# motorcontrol.net
KiCad netlist of a schematic drawn in EAGLE
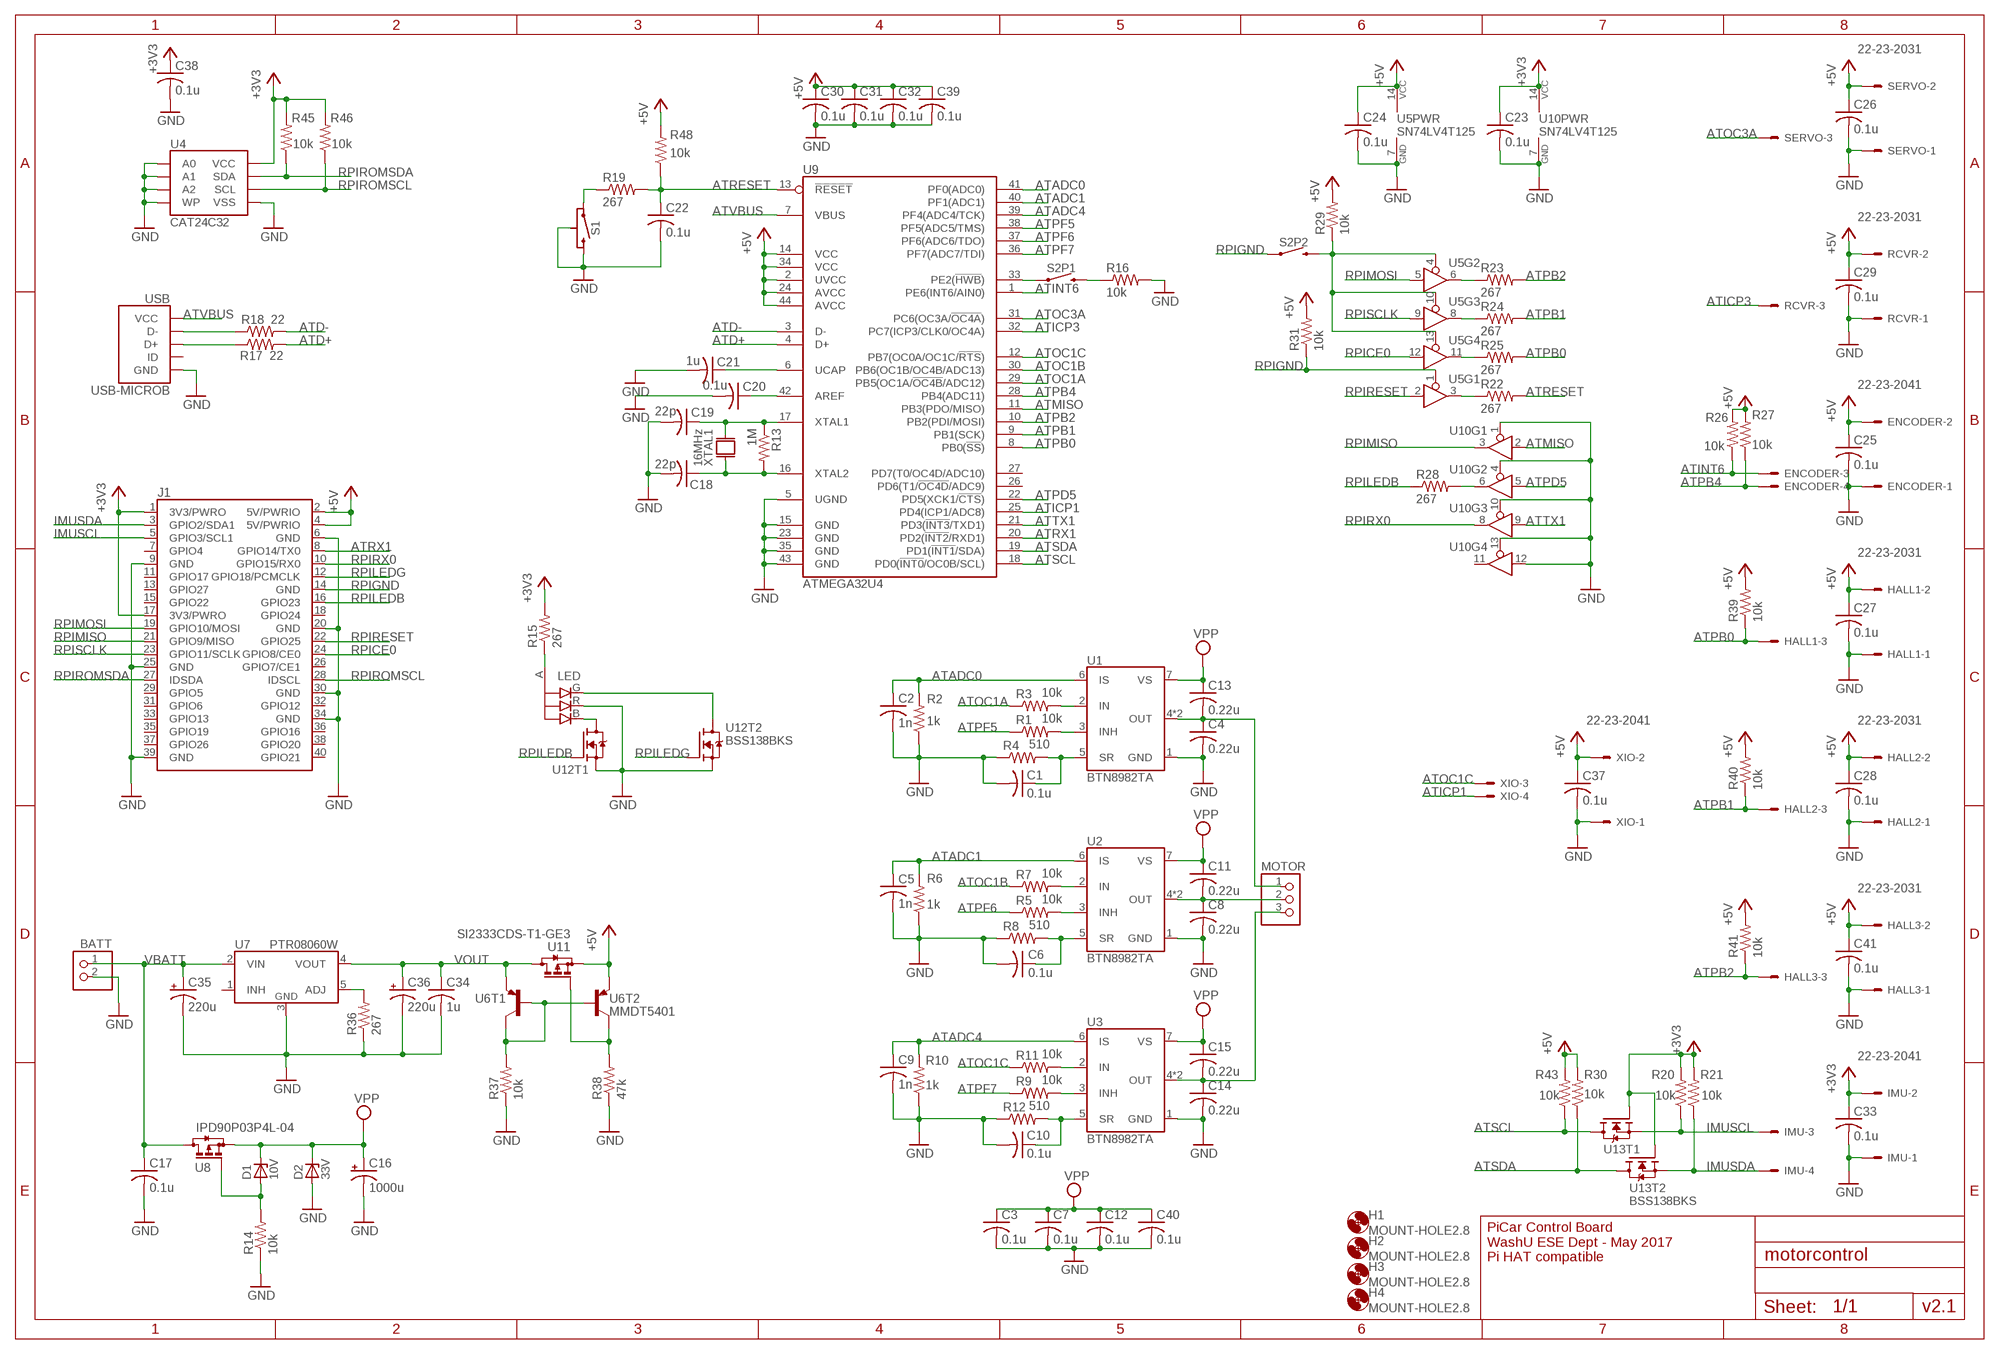
[diagram p0: schematic, sheet 1]

(export (version "E")
  (design (tool "Eeschema 10.0.6"))
  (components
    (comp (ref "BATT")
      (value "ULTRAFIT_2CIRCVCLIP")
      (footprint "eagle-import:ULTRAFIT_2CIRC_VERTCLIP")
      (libsource (lib "eagle-import") (part "ULTRAFIT_2CIRCVCLIP"))
    )
    (comp (ref "C1")
      (value "0.1u")
      (footprint "eagle-import:C1206")
      (libsource (lib "eagle-import") (part "C-USC1206"))
    )
    (comp (ref "C2")
      (value "1n")
      (footprint "eagle-import:C1206")
      (libsource (lib "eagle-import") (part "C-USC1206"))
    )
    (comp (ref "C3")
      (value "0.1u")
      (footprint "eagle-import:C1206")
      (libsource (lib "eagle-import") (part "C-USC1206"))
    )
    (comp (ref "C4")
      (value "0.22u")
      (footprint "eagle-import:C1206")
      (libsource (lib "eagle-import") (part "C-USC1206"))
    )
    (comp (ref "C5")
      (value "1n")
      (footprint "eagle-import:C1206")
      (libsource (lib "eagle-import") (part "C-USC1206"))
    )
    (comp (ref "C6")
      (value "0.1u")
      (footprint "eagle-import:C1206")
      (libsource (lib "eagle-import") (part "C-USC1206"))
    )
    (comp (ref "C7")
      (value "0.1u")
      (footprint "eagle-import:C1206")
      (libsource (lib "eagle-import") (part "C-USC1206"))
    )
    (comp (ref "C8")
      (value "0.22u")
      (footprint "eagle-import:C1206")
      (libsource (lib "eagle-import") (part "C-USC1206"))
    )
    (comp (ref "C9")
      (value "1n")
      (footprint "eagle-import:C1206")
      (libsource (lib "eagle-import") (part "C-USC1206"))
    )
    (comp (ref "C10")
      (value "0.1u")
      (footprint "eagle-import:C1206")
      (libsource (lib "eagle-import") (part "C-USC1206"))
    )
    (comp (ref "C11")
      (value "0.22u")
      (footprint "eagle-import:C1206")
      (libsource (lib "eagle-import") (part "C-USC1206"))
    )
    (comp (ref "C12")
      (value "0.1u")
      (footprint "eagle-import:C1206")
      (libsource (lib "eagle-import") (part "C-USC1206"))
    )
    (comp (ref "C13")
      (value "0.22u")
      (footprint "eagle-import:C1206")
      (libsource (lib "eagle-import") (part "C-USC1206"))
    )
    (comp (ref "C14")
      (value "0.22u")
      (footprint "eagle-import:C1206")
      (libsource (lib "eagle-import") (part "C-USC1206"))
    )
    (comp (ref "C15")
      (value "0.22u")
      (footprint "eagle-import:C1206")
      (libsource (lib "eagle-import") (part "C-USC1206"))
    )
    (comp (ref "C16")
      (value "1000u")
      (footprint "eagle-import:E5-10,5")
      (libsource (lib "eagle-import") (part "CPOL-USE5-10.5"))
    )
    (comp (ref "C17")
      (value "0.1u")
      (footprint "eagle-import:C1206")
      (libsource (lib "eagle-import") (part "C-USC1206"))
    )
    (comp (ref "C18")
      (value "22p")
      (footprint "eagle-import:C1206")
      (libsource (lib "eagle-import") (part "C-USC1206"))
    )
    (comp (ref "C19")
      (value "22p")
      (footprint "eagle-import:C1206")
      (libsource (lib "eagle-import") (part "C-USC1206"))
    )
    (comp (ref "C20")
      (value "0.1u")
      (footprint "eagle-import:C1206")
      (libsource (lib "eagle-import") (part "C-USC1206"))
    )
    (comp (ref "C21")
      (value "1u")
      (footprint "eagle-import:C1206")
      (libsource (lib "eagle-import") (part "C-USC1206"))
    )
    (comp (ref "C22")
      (value "0.1u")
      (footprint "eagle-import:C1206")
      (libsource (lib "eagle-import") (part "C-USC1206"))
    )
    (comp (ref "C23")
      (value "0.1u")
      (footprint "eagle-import:C1206")
      (libsource (lib "eagle-import") (part "C-USC1206"))
    )
    (comp (ref "C24")
      (value "0.1u")
      (footprint "eagle-import:C1206")
      (libsource (lib "eagle-import") (part "C-USC1206"))
    )
    (comp (ref "C25")
      (value "0.1u")
      (footprint "eagle-import:C1206")
      (libsource (lib "eagle-import") (part "C-USC1206"))
    )
    (comp (ref "C26")
      (value "0.1u")
      (footprint "eagle-import:C1206")
      (libsource (lib "eagle-import") (part "C-USC1206"))
    )
    (comp (ref "C27")
      (value "0.1u")
      (footprint "eagle-import:C1206")
      (libsource (lib "eagle-import") (part "C-USC1206"))
    )
    (comp (ref "C28")
      (value "0.1u")
      (footprint "eagle-import:C1206")
      (libsource (lib "eagle-import") (part "C-USC1206"))
    )
    (comp (ref "C29")
      (value "0.1u")
      (footprint "eagle-import:C1206")
      (libsource (lib "eagle-import") (part "C-USC1206"))
    )
    (comp (ref "C30")
      (value "0.1u")
      (footprint "eagle-import:C1206")
      (libsource (lib "eagle-import") (part "C-USC1206"))
    )
    (comp (ref "C31")
      (value "0.1u")
      (footprint "eagle-import:C1206")
      (libsource (lib "eagle-import") (part "C-USC1206"))
    )
    (comp (ref "C32")
      (value "0.1u")
      (footprint "eagle-import:C1206")
      (libsource (lib "eagle-import") (part "C-USC1206"))
    )
    (comp (ref "C33")
      (value "0.1u")
      (footprint "eagle-import:C1206")
      (libsource (lib "eagle-import") (part "C-USC1206"))
    )
    (comp (ref "C34")
      (value "1u")
      (footprint "eagle-import:C1206")
      (libsource (lib "eagle-import") (part "C-USC1206"))
    )
    (comp (ref "C35")
      (value "220u")
      (footprint "eagle-import:E3,5-8")
      (libsource (lib "eagle-import") (part "CPOL-USE3.5-8"))
    )
    (comp (ref "C36")
      (value "220u")
      (footprint "eagle-import:E3,5-8")
      (libsource (lib "eagle-import") (part "CPOL-USE3.5-8"))
    )
    (comp (ref "C37")
      (value "0.1u")
      (footprint "eagle-import:C1206")
      (libsource (lib "eagle-import") (part "C-USC1206"))
    )
    (comp (ref "C38")
      (value "0.1u")
      (footprint "eagle-import:C1206")
      (libsource (lib "eagle-import") (part "C-USC1206"))
    )
    (comp (ref "C39")
      (value "0.1u")
      (footprint "eagle-import:C1206")
      (libsource (lib "eagle-import") (part "C-USC1206"))
    )
    (comp (ref "C40")
      (value "0.1u")
      (footprint "eagle-import:C1206")
      (libsource (lib "eagle-import") (part "C-USC1206"))
    )
    (comp (ref "C41")
      (value "0.1u")
      (footprint "eagle-import:C1206")
      (libsource (lib "eagle-import") (part "C-USC1206"))
    )
    (comp (ref "D1")
      (value "10V")
      (footprint "eagle-import:SOD123")
      (libsource (lib "eagle-import") (part "ZENER_DIODESOD123"))
    )
    (comp (ref "D2")
      (value "33V")
      (footprint "eagle-import:SMA")
      (libsource (lib "eagle-import") (part "ZENER_DIODESMA"))
    )
    (comp (ref "ENCODER")
      (value "22-23-2041")
      (footprint "eagle-import:22-23-2041")
      (fields (field (name "MF") "MOLEX"))
      (libsource (lib "eagle-import") (part "22-23-2041"))
    )
    (comp (ref "H1")
      (value "MOUNT-HOLE2.8")
      (footprint "eagle-import:2,8")
      (libsource (lib "eagle-import") (part "MOUNT-HOLE2.8"))
    )
    (comp (ref "H2")
      (value "MOUNT-HOLE2.8")
      (footprint "eagle-import:2,8")
      (libsource (lib "eagle-import") (part "MOUNT-HOLE2.8"))
    )
    (comp (ref "H3")
      (value "MOUNT-HOLE2.8")
      (footprint "eagle-import:2,8")
      (libsource (lib "eagle-import") (part "MOUNT-HOLE2.8"))
    )
    (comp (ref "H4")
      (value "MOUNT-HOLE2.8")
      (footprint "eagle-import:2,8")
      (libsource (lib "eagle-import") (part "MOUNT-HOLE2.8"))
    )
    (comp (ref "HALL1")
      (value "22-23-2031")
      (footprint "eagle-import:22-23-2031")
      (fields (field (name "MF") "MOLEX"))
      (libsource (lib "eagle-import") (part "22-23-2031"))
    )
    (comp (ref "HALL2")
      (value "22-23-2031")
      (footprint "eagle-import:22-23-2031")
      (fields (field (name "MF") "MOLEX"))
      (libsource (lib "eagle-import") (part "22-23-2031"))
    )
    (comp (ref "HALL3")
      (value "22-23-2031")
      (footprint "eagle-import:22-23-2031")
      (fields (field (name "MF") "MOLEX"))
      (libsource (lib "eagle-import") (part "22-23-2031"))
    )
    (comp (ref "IMU")
      (value "22-23-2041")
      (footprint "eagle-import:22-23-2041")
      (fields (field (name "MF") "MOLEX"))
      (libsource (lib "eagle-import") (part "22-23-2041"))
    )
    (comp (ref "J1")
      (value "RPIHEADER_2.54-SMD")
      (footprint "eagle-import:RPI_SMD")
      (libsource (lib "eagle-import") (part "RPIHEADER_2.54-SMD"))
    )
    (comp (ref "LED")
      (value "LED_3COLOR_COMMONA1411")
      (footprint "eagle-import:150141M173100")
      (libsource (lib "eagle-import") (part "LED_3COLOR_COMMONA1411"))
    )
    (comp (ref "MOTOR")
      (value "ULTRAFIT_3CIRCVCLIP")
      (footprint "eagle-import:ULTRAFIT_3CIRC_VERTCLIP")
      (libsource (lib "eagle-import") (part "ULTRAFIT_3CIRCVCLIP"))
    )
    (comp (ref "R1")
      (value "10k")
      (footprint "eagle-import:R1206")
      (libsource (lib "eagle-import") (part "R-US_R1206"))
    )
    (comp (ref "R2")
      (value "1k")
      (footprint "eagle-import:R1206")
      (libsource (lib "eagle-import") (part "R-US_R1206"))
    )
    (comp (ref "R3")
      (value "10k")
      (footprint "eagle-import:R1206")
      (libsource (lib "eagle-import") (part "R-US_R1206"))
    )
    (comp (ref "R4")
      (value "510")
      (footprint "eagle-import:R1206")
      (libsource (lib "eagle-import") (part "R-US_R1206"))
    )
    (comp (ref "R5")
      (value "10k")
      (footprint "eagle-import:R1206")
      (libsource (lib "eagle-import") (part "R-US_R1206"))
    )
    (comp (ref "R6")
      (value "1k")
      (footprint "eagle-import:R1206")
      (libsource (lib "eagle-import") (part "R-US_R1206"))
    )
    (comp (ref "R7")
      (value "10k")
      (footprint "eagle-import:R1206")
      (libsource (lib "eagle-import") (part "R-US_R1206"))
    )
    (comp (ref "R8")
      (value "510")
      (footprint "eagle-import:R1206")
      (libsource (lib "eagle-import") (part "R-US_R1206"))
    )
    (comp (ref "R9")
      (value "10k")
      (footprint "eagle-import:R1206")
      (libsource (lib "eagle-import") (part "R-US_R1206"))
    )
    (comp (ref "R10")
      (value "1k")
      (footprint "eagle-import:R1206")
      (libsource (lib "eagle-import") (part "R-US_R1206"))
    )
    (comp (ref "R11")
      (value "10k")
      (footprint "eagle-import:R1206")
      (libsource (lib "eagle-import") (part "R-US_R1206"))
    )
    (comp (ref "R12")
      (value "510")
      (footprint "eagle-import:R1206")
      (libsource (lib "eagle-import") (part "R-US_R1206"))
    )
    (comp (ref "R13")
      (value "1M")
      (footprint "eagle-import:R1206")
      (libsource (lib "eagle-import") (part "R-US_R1206"))
    )
    (comp (ref "R14")
      (value "10k")
      (footprint "eagle-import:R1206")
      (libsource (lib "eagle-import") (part "R-US_R1206"))
    )
    (comp (ref "R15")
      (value "267")
      (footprint "eagle-import:R1206")
      (libsource (lib "eagle-import") (part "R-US_R1206"))
    )
    (comp (ref "R16")
      (value "10k")
      (footprint "eagle-import:R1206")
      (libsource (lib "eagle-import") (part "R-US_R1206"))
    )
    (comp (ref "R17")
      (value "22")
      (footprint "eagle-import:R1206")
      (libsource (lib "eagle-import") (part "R-US_R1206"))
    )
    (comp (ref "R18")
      (value "22")
      (footprint "eagle-import:R1206")
      (libsource (lib "eagle-import") (part "R-US_R1206"))
    )
    (comp (ref "R19")
      (value "267")
      (footprint "eagle-import:R1206")
      (libsource (lib "eagle-import") (part "R-US_R1206"))
    )
    (comp (ref "R20")
      (value "10k")
      (footprint "eagle-import:R1206")
      (libsource (lib "eagle-import") (part "R-US_R1206"))
    )
    (comp (ref "R21")
      (value "10k")
      (footprint "eagle-import:R1206")
      (libsource (lib "eagle-import") (part "R-US_R1206"))
    )
    (comp (ref "R22")
      (value "267")
      (footprint "eagle-import:R1206")
      (libsource (lib "eagle-import") (part "R-US_R1206"))
    )
    (comp (ref "R23")
      (value "267")
      (footprint "eagle-import:R1206")
      (libsource (lib "eagle-import") (part "R-US_R1206"))
    )
    (comp (ref "R24")
      (value "267")
      (footprint "eagle-import:R1206")
      (libsource (lib "eagle-import") (part "R-US_R1206"))
    )
    (comp (ref "R25")
      (value "267")
      (footprint "eagle-import:R1206")
      (libsource (lib "eagle-import") (part "R-US_R1206"))
    )
    (comp (ref "R26")
      (value "10k")
      (footprint "eagle-import:R1206")
      (libsource (lib "eagle-import") (part "R-US_R1206"))
    )
    (comp (ref "R27")
      (value "10k")
      (footprint "eagle-import:R1206")
      (libsource (lib "eagle-import") (part "R-US_R1206"))
    )
    (comp (ref "R28")
      (value "267")
      (footprint "eagle-import:R1206")
      (libsource (lib "eagle-import") (part "R-US_R1206"))
    )
    (comp (ref "R29")
      (value "10k")
      (footprint "eagle-import:R1206")
      (libsource (lib "eagle-import") (part "R-US_R1206"))
    )
    (comp (ref "R30")
      (value "10k")
      (footprint "eagle-import:R1206")
      (libsource (lib "eagle-import") (part "R-US_R1206"))
    )
    (comp (ref "R31")
      (value "10k")
      (footprint "eagle-import:R1206")
      (libsource (lib "eagle-import") (part "R-US_R1206"))
    )
    (comp (ref "R36")
      (value "267")
      (footprint "eagle-import:R1206")
      (libsource (lib "eagle-import") (part "R-US_R1206"))
    )
    (comp (ref "R37")
      (value "10k")
      (footprint "eagle-import:R1206")
      (libsource (lib "eagle-import") (part "R-US_R1206"))
    )
    (comp (ref "R38")
      (value "47k")
      (footprint "eagle-import:R1206")
      (libsource (lib "eagle-import") (part "R-US_R1206"))
    )
    (comp (ref "R39")
      (value "10k")
      (footprint "eagle-import:R1206")
      (libsource (lib "eagle-import") (part "R-US_R1206"))
    )
    (comp (ref "R40")
      (value "10k")
      (footprint "eagle-import:R1206")
      (libsource (lib "eagle-import") (part "R-US_R1206"))
    )
    (comp (ref "R41")
      (value "10k")
      (footprint "eagle-import:R1206")
      (libsource (lib "eagle-import") (part "R-US_R1206"))
    )
    (comp (ref "R43")
      (value "10k")
      (footprint "eagle-import:R1206")
      (libsource (lib "eagle-import") (part "R-US_R1206"))
    )
    (comp (ref "R45")
      (value "10k")
      (footprint "eagle-import:R1206")
      (libsource (lib "eagle-import") (part "R-US_R1206"))
    )
    (comp (ref "R46")
      (value "10k")
      (footprint "eagle-import:R1206")
      (libsource (lib "eagle-import") (part "R-US_R1206"))
    )
    (comp (ref "R48")
      (value "10k")
      (footprint "eagle-import:R1206")
      (libsource (lib "eagle-import") (part "R-US_R1206"))
    )
    (comp (ref "RCVR")
      (value "22-23-2031")
      (footprint "eagle-import:22-23-2031")
      (fields (field (name "MF") "MOLEX"))
      (libsource (lib "eagle-import") (part "22-23-2031"))
    )
    (comp (ref "S1")
      (value "SWITCH-GND")
      (footprint "eagle-import:B3F-312X")
      (libsource (lib "eagle-import") (part "SWITCH-GND"))
    )
    (comp (ref "S2")
      (value "A6HF-2DIP")
      (footprint "eagle-import:A6HF-2DIP")
      (libsource (lib "eagle-import") (part "A6HF-2DIP"))
    )
    (comp (ref "SERVO")
      (value "22-23-2031")
      (footprint "eagle-import:22-23-2031")
      (fields (field (name "MF") "MOLEX"))
      (libsource (lib "eagle-import") (part "22-23-2031"))
    )
    (comp (ref "U1")
      (value "BTN8982TA")
      (footprint "eagle-import:TO263-7")
      (libsource (lib "eagle-import") (part "BTN8982TA"))
    )
    (comp (ref "U2")
      (value "BTN8982TA")
      (footprint "eagle-import:TO263-7")
      (libsource (lib "eagle-import") (part "BTN8982TA"))
    )
    (comp (ref "U3")
      (value "BTN8982TA")
      (footprint "eagle-import:TO263-7")
      (libsource (lib "eagle-import") (part "BTN8982TA"))
    )
    (comp (ref "U4")
      (value "CAT24C32")
      (footprint "eagle-import:SOIC8")
      (libsource (lib "eagle-import") (part "CAT24C32"))
    )
    (comp (ref "U5")
      (value "SN74LV4T125")
      (footprint "eagle-import:TSSOP14")
      (libsource (lib "eagle-import") (part "SN74LV4T125"))
    )
    (comp (ref "U6")
      (value "MMDT5401")
      (footprint "eagle-import:SOT363")
      (libsource (lib "eagle-import") (part "MMDT5401"))
    )
    (comp (ref "U7")
      (value "PTR08060W")
      (footprint "eagle-import:EDP_MODULE")
      (libsource (lib "eagle-import") (part "PTR08060W"))
    )
    (comp (ref "U8")
      (value "IPD90P03P4L-04")
      (footprint "eagle-import:TO252-3-11")
      (libsource (lib "eagle-import") (part "IPD90P03P4L-04"))
    )
    (comp (ref "U9")
      (value "ATMEGA32U4")
      (footprint "eagle-import:TQFP44")
      (libsource (lib "eagle-import") (part "ATMEGA32U4"))
    )
    (comp (ref "U10")
      (value "SN74LV4T125")
      (footprint "eagle-import:TSSOP14")
      (libsource (lib "eagle-import") (part "SN74LV4T125"))
    )
    (comp (ref "U11")
      (value "SI2333CDS-T1-GE3")
      (footprint "eagle-import:SOT23-3")
      (libsource (lib "eagle-import") (part "SI2333CDS-T1-GE3"))
    )
    (comp (ref "U12")
      (value "BSS138BKS")
      (footprint "eagle-import:SOT363")
      (libsource (lib "eagle-import") (part "BSS138BKS"))
    )
    (comp (ref "U13")
      (value "BSS138BKS")
      (footprint "eagle-import:SOT363")
      (libsource (lib "eagle-import") (part "BSS138BKS"))
    )
    (comp (ref "USB")
      (value "USB-MICROB")
      (footprint "eagle-import:FCI-10103594-0001LF")
      (libsource (lib "eagle-import") (part "USB-MICROB"))
    )
    (comp (ref "XIO")
      (value "22-23-2041")
      (footprint "eagle-import:22-23-2041")
      (fields (field (name "MF") "MOLEX"))
      (libsource (lib "eagle-import") (part "22-23-2041"))
    )
    (comp (ref "XTAL1")
      (value "16MHz")
      (footprint "eagle-import:ABLS7M2")
      (libsource (lib "eagle-import") (part "XTALABLS7M2"))
    )
  )
  (nets
    (net (code "1") (name "+3V3") (class "Default")
      (node (ref "C23") (pin "1") (pinfunction "1_1") (pintype "passive"))
      (node (ref "C33") (pin "1") (pinfunction "1_1") (pintype "passive"))
      (node (ref "C38") (pin "1") (pinfunction "1_1") (pintype "passive"))
      (node (ref "IMU") (pin "2") (pinfunction "S_2") (pintype "passive"))
      (node (ref "J1") (pin "1") (pinfunction "3V3/PWRO_1") (pintype "passive"))
      (node (ref "J1") (pin "17") (pinfunction "3V3/PWRO_17") (pintype "passive"))
      (node (ref "R15") (pin "2") (pinfunction "2_2") (pintype "passive"))
      (node (ref "R20") (pin "2") (pinfunction "2_2") (pintype "passive"))
      (node (ref "R21") (pin "2") (pinfunction "2_2") (pintype "passive"))
      (node (ref "R45") (pin "2") (pinfunction "2_2") (pintype "passive"))
      (node (ref "R46") (pin "2") (pinfunction "2_2") (pintype "passive"))
      (node (ref "U10") (pin "14") (pinfunction "VCC_14") (pintype "power_in"))
      (node (ref "U13") (pin "2") (pinfunction "G_2") (pintype "passive"))
      (node (ref "U13") (pin "5") (pinfunction "G_5") (pintype "passive"))
      (node (ref "U4") (pin "8") (pinfunction "VCC_8") (pintype "power_in"))
    )
    (net (code "2") (name "+5V") (class "Default")
      (node (ref "C24") (pin "1") (pinfunction "1_1") (pintype "passive"))
      (node (ref "C25") (pin "1") (pinfunction "1_1") (pintype "passive"))
      (node (ref "C26") (pin "1") (pinfunction "1_1") (pintype "passive"))
      (node (ref "C27") (pin "1") (pinfunction "1_1") (pintype "passive"))
      (node (ref "C28") (pin "1") (pinfunction "1_1") (pintype "passive"))
      (node (ref "C29") (pin "1") (pinfunction "1_1") (pintype "passive"))
      (node (ref "C30") (pin "1") (pinfunction "1_1") (pintype "passive"))
      (node (ref "C31") (pin "1") (pinfunction "1_1") (pintype "passive"))
      (node (ref "C32") (pin "1") (pinfunction "1_1") (pintype "passive"))
      (node (ref "C37") (pin "1") (pinfunction "1_1") (pintype "passive"))
      (node (ref "C39") (pin "1") (pinfunction "1_1") (pintype "passive"))
      (node (ref "C41") (pin "1") (pinfunction "1_1") (pintype "passive"))
      (node (ref "ENCODER") (pin "2") (pinfunction "S_2") (pintype "passive"))
      (node (ref "HALL1") (pin "2") (pinfunction "S_2") (pintype "passive"))
      (node (ref "HALL2") (pin "2") (pinfunction "S_2") (pintype "passive"))
      (node (ref "HALL3") (pin "2") (pinfunction "S_2") (pintype "passive"))
      (node (ref "J1") (pin "2") (pinfunction "5V/PWRIO_2") (pintype "passive"))
      (node (ref "J1") (pin "4") (pinfunction "5V/PWRIO_4") (pintype "passive"))
      (node (ref "R26") (pin "2") (pinfunction "2_2") (pintype "passive"))
      (node (ref "R27") (pin "2") (pinfunction "2_2") (pintype "passive"))
      (node (ref "R29") (pin "2") (pinfunction "2_2") (pintype "passive"))
      (node (ref "R30") (pin "2") (pinfunction "2_2") (pintype "passive"))
      (node (ref "R31") (pin "2") (pinfunction "2_2") (pintype "passive"))
      (node (ref "R39") (pin "2") (pinfunction "2_2") (pintype "passive"))
      (node (ref "R40") (pin "2") (pinfunction "2_2") (pintype "passive"))
      (node (ref "R41") (pin "2") (pinfunction "2_2") (pintype "passive"))
      (node (ref "R43") (pin "2") (pinfunction "2_2") (pintype "passive"))
      (node (ref "R48") (pin "2") (pinfunction "2_2") (pintype "passive"))
      (node (ref "RCVR") (pin "2") (pinfunction "S_2") (pintype "passive"))
      (node (ref "SERVO") (pin "2") (pinfunction "S_2") (pintype "passive"))
      (node (ref "U11") (pin "2") (pinfunction "S_2") (pintype "passive"))
      (node (ref "U5") (pin "14") (pinfunction "VCC_14") (pintype "power_in"))
      (node (ref "U6") (pin "4") (pinfunction "E_4") (pintype "passive"))
      (node (ref "U9") (pin "14") (pinfunction "VCC_14") (pintype "bidirectional"))
      (node (ref "U9") (pin "2") (pinfunction "UVCC_2") (pintype "bidirectional"))
      (node (ref "U9") (pin "24") (pinfunction "AVCC_24") (pintype "bidirectional"))
      (node (ref "U9") (pin "34") (pinfunction "VCC_34") (pintype "bidirectional"))
      (node (ref "U9") (pin "44") (pinfunction "AVCC_44") (pintype "bidirectional"))
      (node (ref "XIO") (pin "2") (pinfunction "S_2") (pintype "passive"))
    )
    (net (code "3") (name "/ATADC0") (class "Default")
      (node (ref "C2") (pin "1") (pinfunction "1_1") (pintype "passive"))
      (node (ref "R2") (pin "2") (pinfunction "2_2") (pintype "passive"))
      (node (ref "U1") (pin "6") (pinfunction "IS_6") (pintype "output"))
      (node (ref "U9") (pin "41") (pinfunction "PF0(ADC0)_41") (pintype "bidirectional"))
    )
    (net (code "4") (name "/ATADC1") (class "Default")
      (node (ref "C5") (pin "1") (pinfunction "1_1") (pintype "passive"))
      (node (ref "R6") (pin "2") (pinfunction "2_2") (pintype "passive"))
      (node (ref "U2") (pin "6") (pinfunction "IS_6") (pintype "output"))
      (node (ref "U9") (pin "40") (pinfunction "PF1(ADC1)_40") (pintype "bidirectional"))
    )
    (net (code "5") (name "/ATADC4") (class "Default")
      (node (ref "C9") (pin "1") (pinfunction "1_1") (pintype "passive"))
      (node (ref "R10") (pin "2") (pinfunction "2_2") (pintype "passive"))
      (node (ref "U3") (pin "6") (pinfunction "IS_6") (pintype "output"))
      (node (ref "U9") (pin "39") (pinfunction "PF4(ADC4/TCK)_39") (pintype "bidirectional"))
    )
    (net (code "6") (name "/ATD+") (class "Default")
      (node (ref "R17") (pin "2") (pinfunction "2_2") (pintype "passive"))
      (node (ref "U9") (pin "4") (pinfunction "D+_4") (pintype "bidirectional"))
    )
    (net (code "7") (name "/ATD-") (class "Default")
      (node (ref "R18") (pin "2") (pinfunction "2_2") (pintype "passive"))
      (node (ref "U9") (pin "3") (pinfunction "D-_3") (pintype "bidirectional"))
    )
    (net (code "8") (name "/ATICP1") (class "Default")
      (node (ref "U9") (pin "25") (pinfunction "PD4(ICP1/ADC8)_25") (pintype "bidirectional"))
      (node (ref "XIO") (pin "4") (pinfunction "S_4") (pintype "passive"))
    )
    (net (code "9") (name "/ATICP3") (class "Default")
      (node (ref "RCVR") (pin "3") (pinfunction "S_3") (pintype "passive"))
      (node (ref "U9") (pin "32") (pinfunction "PC7(ICP3/CLK0/OC4A)_32") (pintype "bidirectional"))
    )
    (net (code "10") (name "/ATINT6") (class "Default")
      (node (ref "ENCODER") (pin "3") (pinfunction "S_3") (pintype "passive"))
      (node (ref "R26") (pin "1") (pinfunction "1_1") (pintype "passive"))
      (node (ref "U9") (pin "1") (pinfunction "PE6(INT6/AIN0)_1") (pintype "bidirectional"))
    )
    (net (code "11") (name "/ATMISO") (class "Default")
      (node (ref "U10") (pin "2") (pinfunction "I_2") (pintype "input"))
      (node (ref "U9") (pin "11") (pinfunction "PB3(PDO/MISO)_11") (pintype "bidirectional"))
    )
    (net (code "12") (name "/ATOC1A") (class "Default")
      (node (ref "R3") (pin "1") (pinfunction "1_1") (pintype "passive"))
      (node (ref "U9") (pin "29") (pinfunction "PB5(OC1A/~{OC4B}/ADC12)_29") (pintype "bidirectional"))
    )
    (net (code "13") (name "/ATOC1B") (class "Default")
      (node (ref "R7") (pin "1") (pinfunction "1_1") (pintype "passive"))
      (node (ref "U9") (pin "30") (pinfunction "PB6(OC1B/OC4B/ADC13)_30") (pintype "bidirectional"))
    )
    (net (code "14") (name "/ATOC1C") (class "Default")
      (node (ref "R11") (pin "1") (pinfunction "1_1") (pintype "passive"))
      (node (ref "U9") (pin "12") (pinfunction "PB7(OC0A/OC1C/~{RTS})_12") (pintype "bidirectional"))
      (node (ref "XIO") (pin "3") (pinfunction "S_3") (pintype "passive"))
    )
    (net (code "15") (name "/ATOC3A") (class "Default")
      (node (ref "SERVO") (pin "3") (pinfunction "S_3") (pintype "passive"))
      (node (ref "U9") (pin "31") (pinfunction "PC6(OC3A/~{OC4A})_31") (pintype "bidirectional"))
    )
    (net (code "16") (name "/ATPB0") (class "Default")
      (node (ref "HALL1") (pin "3") (pinfunction "S_3") (pintype "passive"))
      (node (ref "R25") (pin "2") (pinfunction "2_2") (pintype "passive"))
      (node (ref "R39") (pin "1") (pinfunction "1_1") (pintype "passive"))
      (node (ref "U9") (pin "8") (pinfunction "PB0(~{SS})_8") (pintype "bidirectional"))
    )
    (net (code "17") (name "/ATPB1") (class "Default")
      (node (ref "HALL2") (pin "3") (pinfunction "S_3") (pintype "passive"))
      (node (ref "R24") (pin "2") (pinfunction "2_2") (pintype "passive"))
      (node (ref "R40") (pin "1") (pinfunction "1_1") (pintype "passive"))
      (node (ref "U9") (pin "9") (pinfunction "PB1(SCK)_9") (pintype "bidirectional"))
    )
    (net (code "18") (name "/ATPB2") (class "Default")
      (node (ref "HALL3") (pin "3") (pinfunction "S_3") (pintype "passive"))
      (node (ref "R23") (pin "2") (pinfunction "2_2") (pintype "passive"))
      (node (ref "R41") (pin "1") (pinfunction "1_1") (pintype "passive"))
      (node (ref "U9") (pin "10") (pinfunction "PB2(PDI/MOSI)_10") (pintype "bidirectional"))
    )
    (net (code "19") (name "/ATPB4") (class "Default")
      (node (ref "ENCODER") (pin "4") (pinfunction "S_4") (pintype "passive"))
      (node (ref "R27") (pin "1") (pinfunction "1_1") (pintype "passive"))
      (node (ref "U9") (pin "28") (pinfunction "PB4(ADC11)_28") (pintype "bidirectional"))
    )
    (net (code "20") (name "/ATPD5") (class "Default")
      (node (ref "U10") (pin "5") (pinfunction "I_5") (pintype "input"))
      (node (ref "U9") (pin "22") (pinfunction "PD5(XCK1/~{CTS})_22") (pintype "bidirectional"))
    )
    (net (code "21") (name "/ATPF5") (class "Default")
      (node (ref "R1") (pin "1") (pinfunction "1_1") (pintype "passive"))
      (node (ref "U9") (pin "38") (pinfunction "PF5(ADC5/TMS)_38") (pintype "bidirectional"))
    )
    (net (code "22") (name "/ATPF6") (class "Default")
      (node (ref "R5") (pin "1") (pinfunction "1_1") (pintype "passive"))
      (node (ref "U9") (pin "37") (pinfunction "PF6(ADC6/TDO)_37") (pintype "bidirectional"))
    )
    (net (code "23") (name "/ATPF7") (class "Default")
      (node (ref "R9") (pin "1") (pinfunction "1_1") (pintype "passive"))
      (node (ref "U9") (pin "36") (pinfunction "PF7(ADC7/TDI)_36") (pintype "bidirectional"))
    )
    (net (code "24") (name "/ATRESET") (class "Default")
      (node (ref "C22") (pin "1") (pinfunction "1_1") (pintype "passive"))
      (node (ref "R19") (pin "2") (pinfunction "2_2") (pintype "passive"))
      (node (ref "R22") (pin "2") (pinfunction "2_2") (pintype "passive"))
      (node (ref "R48") (pin "1") (pinfunction "1_1") (pintype "passive"))
      (node (ref "U9") (pin "13") (pinfunction "~{RESET}_13") (pintype "bidirectional"))
    )
    (net (code "25") (name "/ATRX1") (class "Default")
      (node (ref "J1") (pin "8") (pinfunction "GPIO14/TX0_8") (pintype "passive"))
      (node (ref "U9") (pin "20") (pinfunction "PD2(~{INT2}/RXD1)_20") (pintype "bidirectional"))
    )
    (net (code "26") (name "/ATSCL") (class "Default")
      (node (ref "R43") (pin "1") (pinfunction "1_1") (pintype "passive"))
      (node (ref "U13") (pin "6") (pinfunction "D_6") (pintype "passive"))
      (node (ref "U9") (pin "18") (pinfunction "PD0(~{INT0}/OC0B/SCL)_18") (pintype "bidirectional"))
    )
    (net (code "27") (name "/ATSDA") (class "Default")
      (node (ref "R30") (pin "1") (pinfunction "1_1") (pintype "passive"))
      (node (ref "U13") (pin "3") (pinfunction "D_3") (pintype "passive"))
      (node (ref "U9") (pin "19") (pinfunction "PD1(~{INT1}/SDA)_19") (pintype "bidirectional"))
    )
    (net (code "28") (name "/ATTX1") (class "Default")
      (node (ref "U10") (pin "9") (pinfunction "I_9") (pintype "input"))
      (node (ref "U9") (pin "21") (pinfunction "PD3(~{INT3}/TXD1)_21") (pintype "bidirectional"))
    )
    (net (code "29") (name "/ATVBUS") (class "Default")
      (node (ref "U9") (pin "7") (pinfunction "VBUS_7") (pintype "bidirectional"))
      (node (ref "USB") (pin "1") (pinfunction "VCC_1") (pintype "passive"))
    )
    (net (code "30") (name "/IMUSCL") (class "Default")
      (node (ref "IMU") (pin "3") (pinfunction "S_3") (pintype "passive"))
      (node (ref "J1") (pin "5") (pinfunction "GPIO3/SCL1_5") (pintype "passive"))
      (node (ref "R20") (pin "1") (pinfunction "1_1") (pintype "passive"))
      (node (ref "U13") (pin "1") (pinfunction "S_1") (pintype "passive"))
    )
    (net (code "31") (name "/IMUSDA") (class "Default")
      (node (ref "IMU") (pin "4") (pinfunction "S_4") (pintype "passive"))
      (node (ref "J1") (pin "3") (pinfunction "GPIO2/SDA1_3") (pintype "passive"))
      (node (ref "R21") (pin "1") (pinfunction "1_1") (pintype "passive"))
      (node (ref "U13") (pin "4") (pinfunction "S_4") (pintype "passive"))
    )
    (net (code "32") (name "/RPICE0") (class "Default")
      (node (ref "J1") (pin "24") (pinfunction "GPIO8/CE0_24") (pintype "passive"))
      (node (ref "U5") (pin "12") (pinfunction "I_12") (pintype "input"))
    )
    (net (code "33") (name "/RPIGND") (class "Default")
      (node (ref "J1") (pin "14") (pinfunction "GND_14") (pintype "passive"))
      (node (ref "R31") (pin "1") (pinfunction "1_1") (pintype "passive"))
      (node (ref "S2") (pin "P2.1") (pinfunction "1_P2.1") (pintype "passive"))
      (node (ref "U5") (pin "1") (pinfunction "OE_1") (pintype "input"))
    )
    (net (code "34") (name "/RPILEDB") (class "Default")
      (node (ref "J1") (pin "16") (pinfunction "GPIO23_16") (pintype "passive"))
      (node (ref "R28") (pin "1") (pinfunction "1_1") (pintype "passive"))
      (node (ref "U12") (pin "2") (pinfunction "G_2") (pintype "passive"))
    )
    (net (code "35") (name "/RPILEDG") (class "Default")
      (node (ref "J1") (pin "12") (pinfunction "GPIO18/PCMCLK_12") (pintype "passive"))
      (node (ref "U12") (pin "5") (pinfunction "G_5") (pintype "passive"))
    )
    (net (code "36") (name "/RPIMISO") (class "Default")
      (node (ref "J1") (pin "21") (pinfunction "GPIO9/MISO_21") (pintype "passive"))
      (node (ref "U10") (pin "3") (pinfunction "O_3") (pintype "tri_state"))
    )
    (net (code "37") (name "/RPIMOSI") (class "Default")
      (node (ref "J1") (pin "19") (pinfunction "GPIO10/MOSI_19") (pintype "passive"))
      (node (ref "U5") (pin "5") (pinfunction "I_5") (pintype "input"))
    )
    (net (code "38") (name "/RPIRESET") (class "Default")
      (node (ref "J1") (pin "22") (pinfunction "GPIO25_22") (pintype "passive"))
      (node (ref "U5") (pin "2") (pinfunction "I_2") (pintype "input"))
    )
    (net (code "39") (name "/RPIROMSCL") (class "Default")
      (node (ref "J1") (pin "28") (pinfunction "IDSCL_28") (pintype "passive"))
      (node (ref "R46") (pin "1") (pinfunction "1_1") (pintype "passive"))
      (node (ref "U4") (pin "6") (pinfunction "SCL_6") (pintype "input"))
    )
    (net (code "40") (name "/RPIROMSDA") (class "Default")
      (node (ref "J1") (pin "27") (pinfunction "IDSDA_27") (pintype "passive"))
      (node (ref "R45") (pin "1") (pinfunction "1_1") (pintype "passive"))
      (node (ref "U4") (pin "5") (pinfunction "SDA_5") (pintype "bidirectional"))
    )
    (net (code "41") (name "/RPIRX0") (class "Default")
      (node (ref "J1") (pin "10") (pinfunction "GPIO15/RX0_10") (pintype "passive"))
      (node (ref "U10") (pin "8") (pinfunction "O_8") (pintype "tri_state"))
    )
    (net (code "42") (name "/RPISCLK") (class "Default")
      (node (ref "J1") (pin "23") (pinfunction "GPIO11/SCLK_23") (pintype "passive"))
      (node (ref "U5") (pin "9") (pinfunction "I_9") (pintype "input"))
    )
    (net (code "43") (name "/VBATT") (class "Default")
      (node (ref "BATT") (pin "1") (pinfunction "P1_1") (pintype "passive"))
      (node (ref "C17") (pin "1") (pinfunction "1_1") (pintype "passive"))
      (node (ref "C35") (pin "+") (pinfunction "+_+") (pintype "passive"))
      (node (ref "U7") (pin "2") (pinfunction "VIN_2") (pintype "power_in"))
      (node (ref "U8") (pin "2") (pinfunction "D_2") (pintype "passive"))
    )
    (net (code "44") (name "/VOUT") (class "Default")
      (node (ref "C34") (pin "1") (pinfunction "1_1") (pintype "passive"))
      (node (ref "C36") (pin "+") (pinfunction "+_+") (pintype "passive"))
      (node (ref "U11") (pin "3") (pinfunction "D_3") (pintype "passive"))
      (node (ref "U6") (pin "1") (pinfunction "E_1") (pintype "passive"))
      (node (ref "U7") (pin "4") (pinfunction "VOUT_4") (pintype "power_in"))
    )
    (net (code "45") (name "GND") (class "Default")
      (node (ref "BATT") (pin "2") (pinfunction "P2_2") (pintype "passive"))
      (node (ref "C1") (pin "2") (pinfunction "2_2") (pintype "passive"))
      (node (ref "C10") (pin "2") (pinfunction "2_2") (pintype "passive"))
      (node (ref "C12") (pin "2") (pinfunction "2_2") (pintype "passive"))
      (node (ref "C14") (pin "2") (pinfunction "2_2") (pintype "passive"))
      (node (ref "C16") (pin "-") (pinfunction "-_-") (pintype "passive"))
      (node (ref "C17") (pin "2") (pinfunction "2_2") (pintype "passive"))
      (node (ref "C18") (pin "2") (pinfunction "2_2") (pintype "passive"))
      (node (ref "C19") (pin "2") (pinfunction "2_2") (pintype "passive"))
      (node (ref "C2") (pin "2") (pinfunction "2_2") (pintype "passive"))
      (node (ref "C20") (pin "2") (pinfunction "2_2") (pintype "passive"))
      (node (ref "C21") (pin "2") (pinfunction "2_2") (pintype "passive"))
      (node (ref "C22") (pin "2") (pinfunction "2_2") (pintype "passive"))
      (node (ref "C23") (pin "2") (pinfunction "2_2") (pintype "passive"))
      (node (ref "C24") (pin "2") (pinfunction "2_2") (pintype "passive"))
      (node (ref "C25") (pin "2") (pinfunction "2_2") (pintype "passive"))
      (node (ref "C26") (pin "2") (pinfunction "2_2") (pintype "passive"))
      (node (ref "C27") (pin "2") (pinfunction "2_2") (pintype "passive"))
      (node (ref "C28") (pin "2") (pinfunction "2_2") (pintype "passive"))
      (node (ref "C29") (pin "2") (pinfunction "2_2") (pintype "passive"))
      (node (ref "C3") (pin "2") (pinfunction "2_2") (pintype "passive"))
      (node (ref "C30") (pin "2") (pinfunction "2_2") (pintype "passive"))
      (node (ref "C31") (pin "2") (pinfunction "2_2") (pintype "passive"))
      (node (ref "C32") (pin "2") (pinfunction "2_2") (pintype "passive"))
      (node (ref "C33") (pin "2") (pinfunction "2_2") (pintype "passive"))
      (node (ref "C34") (pin "2") (pinfunction "2_2") (pintype "passive"))
      (node (ref "C35") (pin "-") (pinfunction "-_-") (pintype "passive"))
      (node (ref "C36") (pin "-") (pinfunction "-_-") (pintype "passive"))
      (node (ref "C37") (pin "2") (pinfunction "2_2") (pintype "passive"))
      (node (ref "C38") (pin "2") (pinfunction "2_2") (pintype "passive"))
      (node (ref "C39") (pin "2") (pinfunction "2_2") (pintype "passive"))
      (node (ref "C4") (pin "2") (pinfunction "2_2") (pintype "passive"))
      (node (ref "C40") (pin "2") (pinfunction "2_2") (pintype "passive"))
      (node (ref "C41") (pin "2") (pinfunction "2_2") (pintype "passive"))
      (node (ref "C5") (pin "2") (pinfunction "2_2") (pintype "passive"))
      (node (ref "C6") (pin "2") (pinfunction "2_2") (pintype "passive"))
      (node (ref "C7") (pin "2") (pinfunction "2_2") (pintype "passive"))
      (node (ref "C8") (pin "2") (pinfunction "2_2") (pintype "passive"))
      (node (ref "C9") (pin "2") (pinfunction "2_2") (pintype "passive"))
      (node (ref "D2") (pin "A") (pinfunction "A_A") (pintype "passive"))
      (node (ref "ENCODER") (pin "1") (pinfunction "S_1") (pintype "passive"))
      (node (ref "HALL1") (pin "1") (pinfunction "S_1") (pintype "passive"))
      (node (ref "HALL2") (pin "1") (pinfunction "S_1") (pintype "passive"))
      (node (ref "HALL3") (pin "1") (pinfunction "S_1") (pintype "passive"))
      (node (ref "IMU") (pin "1") (pinfunction "S_1") (pintype "passive"))
      (node (ref "J1") (pin "20") (pinfunction "GND_20") (pintype "passive"))
      (node (ref "J1") (pin "25") (pinfunction "GND_25") (pintype "passive"))
      (node (ref "J1") (pin "30") (pinfunction "GND_30") (pintype "passive"))
      (node (ref "J1") (pin "34") (pinfunction "GND_34") (pintype "passive"))
      (node (ref "J1") (pin "39") (pinfunction "GND_39") (pintype "passive"))
      (node (ref "J1") (pin "6") (pinfunction "GND_6") (pintype "passive"))
      (node (ref "J1") (pin "9") (pinfunction "GND_9") (pintype "passive"))
      (node (ref "LED") (pin "R") (pinfunction "R_R") (pintype "passive"))
      (node (ref "R10") (pin "1") (pinfunction "1_1") (pintype "passive"))
      (node (ref "R12") (pin "1") (pinfunction "1_1") (pintype "passive"))
      (node (ref "R14") (pin "1") (pinfunction "1_1") (pintype "passive"))
      (node (ref "R16") (pin "2") (pinfunction "2_2") (pintype "passive"))
      (node (ref "R2") (pin "1") (pinfunction "1_1") (pintype "passive"))
      (node (ref "R36") (pin "1") (pinfunction "1_1") (pintype "passive"))
      (node (ref "R37") (pin "1") (pinfunction "1_1") (pintype "passive"))
      (node (ref "R38") (pin "1") (pinfunction "1_1") (pintype "passive"))
      (node (ref "R4") (pin "1") (pinfunction "1_1") (pintype "passive"))
      (node (ref "R6") (pin "1") (pinfunction "1_1") (pintype "passive"))
      (node (ref "R8") (pin "1") (pinfunction "1_1") (pintype "passive"))
      (node (ref "RCVR") (pin "1") (pinfunction "S_1") (pintype "passive"))
      (node (ref "S1") (pin "2") (pinfunction "2_2") (pintype "passive"))
      (node (ref "S1") (pin "3") (pinfunction "GND_3") (pintype "passive"))
      (node (ref "S1") (pin "4") (pinfunction "GND_4") (pintype "passive"))
      (node (ref "SERVO") (pin "1") (pinfunction "S_1") (pintype "passive"))
      (node (ref "U1") (pin "1") (pinfunction "GND_1") (pintype "power_in"))
      (node (ref "U10") (pin "1") (pinfunction "OE_1") (pintype "input"))
      (node (ref "U10") (pin "10") (pinfunction "OE_10") (pintype "input"))
      (node (ref "U10") (pin "12") (pinfunction "I_12") (pintype "input"))
      (node (ref "U10") (pin "13") (pinfunction "OE_13") (pintype "input"))
      (node (ref "U10") (pin "4") (pinfunction "OE_4") (pintype "input"))
      (node (ref "U10") (pin "7") (pinfunction "GND_7") (pintype "power_in"))
      (node (ref "U12") (pin "1") (pinfunction "S_1") (pintype "passive"))
      (node (ref "U12") (pin "4") (pinfunction "S_4") (pintype "passive"))
      (node (ref "U2") (pin "1") (pinfunction "GND_1") (pintype "power_in"))
      (node (ref "U3") (pin "1") (pinfunction "GND_1") (pintype "power_in"))
      (node (ref "U4") (pin "1") (pinfunction "A0_1") (pintype "input"))
      (node (ref "U4") (pin "2") (pinfunction "A1_2") (pintype "input"))
      (node (ref "U4") (pin "3") (pinfunction "A2_3") (pintype "input"))
      (node (ref "U4") (pin "4") (pinfunction "VSS_4") (pintype "passive"))
      (node (ref "U4") (pin "7") (pinfunction "WP_7") (pintype "input"))
      (node (ref "U5") (pin "7") (pinfunction "GND_7") (pintype "power_in"))
      (node (ref "U7") (pin "3") (pinfunction "GND_3") (pintype "power_in"))
      (node (ref "U9") (pin "15") (pinfunction "GND_15") (pintype "bidirectional"))
      (node (ref "U9") (pin "23") (pinfunction "GND_23") (pintype "bidirectional"))
      (node (ref "U9") (pin "35") (pinfunction "GND_35") (pintype "bidirectional"))
      (node (ref "U9") (pin "43") (pinfunction "GND_43") (pintype "bidirectional"))
      (node (ref "U9") (pin "5") (pinfunction "UGND_5") (pintype "bidirectional"))
      (node (ref "USB") (pin "5") (pinfunction "GND_5") (pintype "passive"))
      (node (ref "USB") (pin "GND1") (pinfunction "GND_GND1") (pintype "passive"))
      (node (ref "USB") (pin "GND2") (pinfunction "GND_GND2") (pintype "passive"))
      (node (ref "USB") (pin "GND3") (pinfunction "GND_GND3") (pintype "passive"))
      (node (ref "USB") (pin "GND4") (pinfunction "GND_GND4") (pintype "passive"))
      (node (ref "XIO") (pin "1") (pinfunction "S_1") (pintype "passive"))
    )
    (net (code "46") (name "Net-(LED-PadA)") (class "Default")
      (node (ref "LED") (pin "A") (pinfunction "A_A") (pintype "passive"))
      (node (ref "R15") (pin "1") (pinfunction "1_1") (pintype "passive"))
    )
    (net (code "47") (name "Net-(MOTOR-P1)") (class "Default")
      (node (ref "C13") (pin "2") (pinfunction "2_2") (pintype "passive"))
      (node (ref "C4") (pin "1") (pinfunction "1_1") (pintype "passive"))
      (node (ref "MOTOR") (pin "1") (pinfunction "P1_1") (pintype "passive"))
      (node (ref "U1") (pin "4") (pinfunction "OUT_4") (pintype "passive"))
      (node (ref "U1") (pin "8") (pinfunction "OUT_8") (pintype "passive"))
    )
    (net (code "48") (name "Net-(MOTOR-P2)") (class "Default")
      (node (ref "C11") (pin "2") (pinfunction "2_2") (pintype "passive"))
      (node (ref "C8") (pin "1") (pinfunction "1_1") (pintype "passive"))
      (node (ref "MOTOR") (pin "2") (pinfunction "P2_2") (pintype "passive"))
      (node (ref "U2") (pin "4") (pinfunction "OUT_4") (pintype "passive"))
      (node (ref "U2") (pin "8") (pinfunction "OUT_8") (pintype "passive"))
    )
    (net (code "49") (name "Net-(MOTOR-P3)") (class "Default")
      (node (ref "C14") (pin "1") (pinfunction "1_1") (pintype "passive"))
      (node (ref "C15") (pin "2") (pinfunction "2_2") (pintype "passive"))
      (node (ref "MOTOR") (pin "3") (pinfunction "P3_3") (pintype "passive"))
      (node (ref "U3") (pin "4") (pinfunction "OUT_4") (pintype "passive"))
      (node (ref "U3") (pin "8") (pinfunction "OUT_8") (pintype "passive"))
    )
    (net (code "50") (name "Net-(R19-Pad1)") (class "Default")
      (node (ref "R19") (pin "1") (pinfunction "1_1") (pintype "passive"))
      (node (ref "S1") (pin "1") (pinfunction "1_1") (pintype "passive"))
    )
    (net (code "51") (name "Net-(S2A-1)") (class "Default")
      (node (ref "S2") (pin "P1.1") (pinfunction "1_P1.1") (pintype "passive"))
      (node (ref "U9") (pin "33") (pinfunction "PE2(~{HWB})_33") (pintype "bidirectional"))
    )
    (net (code "52") (name "Net-(S2A-2)") (class "Default")
      (node (ref "R16") (pin "1") (pinfunction "1_1") (pintype "passive"))
      (node (ref "S2") (pin "P1.2") (pinfunction "2_P1.2") (pintype "passive"))
    )
    (net (code "53") (name "Net-(S2B-2)") (class "Default")
      (node (ref "R29") (pin "1") (pinfunction "1_1") (pintype "passive"))
      (node (ref "S2") (pin "P2.2") (pinfunction "2_P2.2") (pintype "passive"))
      (node (ref "U5") (pin "10") (pinfunction "OE_10") (pintype "input"))
      (node (ref "U5") (pin "13") (pinfunction "OE_13") (pintype "input"))
      (node (ref "U5") (pin "4") (pinfunction "OE_4") (pintype "input"))
    )
    (net (code "54") (name "Net-(U1-IN)") (class "Default")
      (node (ref "R3") (pin "2") (pinfunction "2_2") (pintype "passive"))
      (node (ref "U1") (pin "2") (pinfunction "IN_2") (pintype "input"))
    )
    (net (code "55") (name "Net-(U1-INH)") (class "Default")
      (node (ref "R1") (pin "2") (pinfunction "2_2") (pintype "passive"))
      (node (ref "U1") (pin "3") (pinfunction "INH_3") (pintype "input"))
    )
    (net (code "56") (name "Net-(U1-SR)") (class "Default")
      (node (ref "C1") (pin "1") (pinfunction "1_1") (pintype "passive"))
      (node (ref "R4") (pin "2") (pinfunction "2_2") (pintype "passive"))
      (node (ref "U1") (pin "5") (pinfunction "SR_5") (pintype "passive"))
    )
    (net (code "57") (name "Net-(U2-IN)") (class "Default")
      (node (ref "R7") (pin "2") (pinfunction "2_2") (pintype "passive"))
      (node (ref "U2") (pin "2") (pinfunction "IN_2") (pintype "input"))
    )
    (net (code "58") (name "Net-(U2-INH)") (class "Default")
      (node (ref "R5") (pin "2") (pinfunction "2_2") (pintype "passive"))
      (node (ref "U2") (pin "3") (pinfunction "INH_3") (pintype "input"))
    )
    (net (code "59") (name "Net-(U2-SR)") (class "Default")
      (node (ref "C6") (pin "1") (pinfunction "1_1") (pintype "passive"))
      (node (ref "R8") (pin "2") (pinfunction "2_2") (pintype "passive"))
      (node (ref "U2") (pin "5") (pinfunction "SR_5") (pintype "passive"))
    )
    (net (code "60") (name "Net-(U3-IN)") (class "Default")
      (node (ref "R11") (pin "2") (pinfunction "2_2") (pintype "passive"))
      (node (ref "U3") (pin "2") (pinfunction "IN_2") (pintype "input"))
    )
    (net (code "61") (name "Net-(U3-INH)") (class "Default")
      (node (ref "R9") (pin "2") (pinfunction "2_2") (pintype "passive"))
      (node (ref "U3") (pin "3") (pinfunction "INH_3") (pintype "input"))
    )
    (net (code "62") (name "Net-(U3-SR)") (class "Default")
      (node (ref "C10") (pin "1") (pinfunction "1_1") (pintype "passive"))
      (node (ref "R12") (pin "2") (pinfunction "2_2") (pintype "passive"))
      (node (ref "U3") (pin "5") (pinfunction "SR_5") (pintype "passive"))
    )
    (net (code "63") (name "Net-(U5A-O)") (class "Default")
      (node (ref "R22") (pin "1") (pinfunction "1_1") (pintype "passive"))
      (node (ref "U5") (pin "3") (pinfunction "O_3") (pintype "tri_state"))
    )
    (net (code "64") (name "Net-(U5B-O)") (class "Default")
      (node (ref "R23") (pin "1") (pinfunction "1_1") (pintype "passive"))
      (node (ref "U5") (pin "6") (pinfunction "O_6") (pintype "tri_state"))
    )
    (net (code "65") (name "Net-(U5C-O)") (class "Default")
      (node (ref "R24") (pin "1") (pinfunction "1_1") (pintype "passive"))
      (node (ref "U5") (pin "8") (pinfunction "O_8") (pintype "tri_state"))
    )
    (net (code "66") (name "Net-(U5D-O)") (class "Default")
      (node (ref "R25") (pin "1") (pinfunction "1_1") (pintype "passive"))
      (node (ref "U5") (pin "11") (pinfunction "O_11") (pintype "tri_state"))
    )
    (net (code "67") (name "Net-(U6A-B)") (class "Default")
      (node (ref "R37") (pin "2") (pinfunction "2_2") (pintype "passive"))
      (node (ref "U6") (pin "2") (pinfunction "B_2") (pintype "passive"))
      (node (ref "U6") (pin "5") (pinfunction "B_5") (pintype "passive"))
      (node (ref "U6") (pin "6") (pinfunction "C_6") (pintype "passive"))
    )
    (net (code "68") (name "Net-(U7-ADJ)") (class "Default")
      (node (ref "R36") (pin "2") (pinfunction "2_2") (pintype "passive"))
      (node (ref "U7") (pin "5") (pinfunction "ADJ_5") (pintype "passive"))
    )
    (net (code "69") (name "Net-(U8-G)") (class "Default")
      (node (ref "D1") (pin "A") (pinfunction "A_A") (pintype "passive"))
      (node (ref "R14") (pin "2") (pinfunction "2_2") (pintype "passive"))
      (node (ref "U8") (pin "1") (pinfunction "G_1") (pintype "passive"))
    )
    (net (code "70") (name "Net-(U9-AREF)") (class "Default")
      (node (ref "C20") (pin "1") (pinfunction "1_1") (pintype "passive"))
      (node (ref "U9") (pin "42") (pinfunction "AREF_42") (pintype "bidirectional"))
    )
    (net (code "71") (name "Net-(U9-UCAP)") (class "Default")
      (node (ref "C21") (pin "1") (pinfunction "1_1") (pintype "passive"))
      (node (ref "U9") (pin "6") (pinfunction "UCAP_6") (pintype "bidirectional"))
    )
    (net (code "72") (name "Net-(U9-XTAL1)") (class "Default")
      (node (ref "C19") (pin "1") (pinfunction "1_1") (pintype "passive"))
      (node (ref "R13") (pin "1") (pinfunction "1_1") (pintype "passive"))
      (node (ref "U9") (pin "17") (pinfunction "XTAL1_17") (pintype "bidirectional"))
      (node (ref "XTAL1") (pin "2") (pinfunction "2_2") (pintype "passive"))
    )
    (net (code "73") (name "Net-(U9-XTAL2)") (class "Default")
      (node (ref "C18") (pin "1") (pinfunction "1_1") (pintype "passive"))
      (node (ref "R13") (pin "2") (pinfunction "2_2") (pintype "passive"))
      (node (ref "U9") (pin "16") (pinfunction "XTAL2_16") (pintype "bidirectional"))
      (node (ref "XTAL1") (pin "1") (pinfunction "1_1") (pintype "passive"))
    )
    (net (code "74") (name "Net-(U10B-O)") (class "Default")
      (node (ref "R28") (pin "2") (pinfunction "2_2") (pintype "passive"))
      (node (ref "U10") (pin "6") (pinfunction "O_6") (pintype "tri_state"))
    )
    (net (code "75") (name "Net-(U11-G)") (class "Default")
      (node (ref "R38") (pin "2") (pinfunction "2_2") (pintype "passive"))
      (node (ref "U11") (pin "1") (pinfunction "G_1") (pintype "passive"))
      (node (ref "U6") (pin "3") (pinfunction "C_3") (pintype "passive"))
    )
    (net (code "76") (name "Net-(U12A-D)") (class "Default")
      (node (ref "LED") (pin "B") (pinfunction "B_B") (pintype "passive"))
      (node (ref "U12") (pin "6") (pinfunction "D_6") (pintype "passive"))
    )
    (net (code "77") (name "Net-(U12B-D)") (class "Default")
      (node (ref "LED") (pin "G") (pinfunction "G_G") (pintype "passive"))
      (node (ref "U12") (pin "3") (pinfunction "D_3") (pintype "passive"))
    )
    (net (code "78") (name "Net-(USB-D+)") (class "Default")
      (node (ref "R17") (pin "1") (pinfunction "1_1") (pintype "passive"))
      (node (ref "USB") (pin "3") (pinfunction "D+_3") (pintype "bidirectional"))
    )
    (net (code "79") (name "Net-(USB-D-)") (class "Default")
      (node (ref "R18") (pin "1") (pinfunction "1_1") (pintype "passive"))
      (node (ref "USB") (pin "2") (pinfunction "D-_2") (pintype "bidirectional"))
    )
    (net (code "80") (name "VPP") (class "Default")
      (node (ref "C11") (pin "1") (pinfunction "1_1") (pintype "passive"))
      (node (ref "C12") (pin "1") (pinfunction "1_1") (pintype "passive"))
      (node (ref "C13") (pin "1") (pinfunction "1_1") (pintype "passive"))
      (node (ref "C15") (pin "1") (pinfunction "1_1") (pintype "passive"))
      (node (ref "C16") (pin "+") (pinfunction "+_+") (pintype "passive"))
      (node (ref "C3") (pin "1") (pinfunction "1_1") (pintype "passive"))
      (node (ref "C40") (pin "1") (pinfunction "1_1") (pintype "passive"))
      (node (ref "C7") (pin "1") (pinfunction "1_1") (pintype "passive"))
      (node (ref "D1") (pin "C") (pinfunction "C_C") (pintype "passive"))
      (node (ref "D2") (pin "C") (pinfunction "C_C") (pintype "passive"))
      (node (ref "U1") (pin "7") (pinfunction "VS_7") (pintype "passive"))
      (node (ref "U2") (pin "7") (pinfunction "VS_7") (pintype "passive"))
      (node (ref "U3") (pin "7") (pinfunction "VS_7") (pintype "passive"))
      (node (ref "U8") (pin "3") (pinfunction "S_3") (pintype "passive"))
    )
    (net (code "81") (name "unconnected-(J1-GPIO4-Pad7)") (class "Default")
      (node (ref "J1") (pin "7") (pinfunction "GPIO4_7") (pintype "passive"))
    )
    (net (code "82") (name "unconnected-(J1-GPIO5-Pad29)") (class "Default")
      (node (ref "J1") (pin "29") (pinfunction "GPIO5_29") (pintype "passive"))
    )
    (net (code "83") (name "unconnected-(J1-GPIO6-Pad31)") (class "Default")
      (node (ref "J1") (pin "31") (pinfunction "GPIO6_31") (pintype "passive"))
    )
    (net (code "84") (name "unconnected-(J1-GPIO7{slash}CE1-Pad26)") (class "Default")
      (node (ref "J1") (pin "26") (pinfunction "GPIO7/CE1_26") (pintype "passive"))
    )
    (net (code "85") (name "unconnected-(J1-GPIO12-Pad32)") (class "Default")
      (node (ref "J1") (pin "32") (pinfunction "GPIO12_32") (pintype "passive"))
    )
    (net (code "86") (name "unconnected-(J1-GPIO13-Pad33)") (class "Default")
      (node (ref "J1") (pin "33") (pinfunction "GPIO13_33") (pintype "passive"))
    )
    (net (code "87") (name "unconnected-(J1-GPIO16-Pad36)") (class "Default")
      (node (ref "J1") (pin "36") (pinfunction "GPIO16_36") (pintype "passive"))
    )
    (net (code "88") (name "unconnected-(J1-GPIO17-Pad11)") (class "Default")
      (node (ref "J1") (pin "11") (pinfunction "GPIO17_11") (pintype "passive"))
    )
    (net (code "89") (name "unconnected-(J1-GPIO19-Pad35)") (class "Default")
      (node (ref "J1") (pin "35") (pinfunction "GPIO19_35") (pintype "passive"))
    )
    (net (code "90") (name "unconnected-(J1-GPIO20-Pad38)") (class "Default")
      (node (ref "J1") (pin "38") (pinfunction "GPIO20_38") (pintype "passive"))
    )
    (net (code "91") (name "unconnected-(J1-GPIO21-Pad40)") (class "Default")
      (node (ref "J1") (pin "40") (pinfunction "GPIO21_40") (pintype "passive"))
    )
    (net (code "92") (name "unconnected-(J1-GPIO22-Pad15)") (class "Default")
      (node (ref "J1") (pin "15") (pinfunction "GPIO22_15") (pintype "passive"))
    )
    (net (code "93") (name "unconnected-(J1-GPIO24-Pad18)") (class "Default")
      (node (ref "J1") (pin "18") (pinfunction "GPIO24_18") (pintype "passive"))
    )
    (net (code "94") (name "unconnected-(J1-GPIO26-Pad37)") (class "Default")
      (node (ref "J1") (pin "37") (pinfunction "GPIO26_37") (pintype "passive"))
    )
    (net (code "95") (name "unconnected-(J1-GPIO27-Pad13)") (class "Default")
      (node (ref "J1") (pin "13") (pinfunction "GPIO27_13") (pintype "passive"))
    )
    (net (code "96") (name "unconnected-(U7-INH-Pad1)") (class "Default")
      (node (ref "U7") (pin "1") (pinfunction "INH_1") (pintype "open_collector"))
    )
    (net (code "97") (name "unconnected-(U9-PD6(T1{slash}~{OC4D}{slash}ADC9)-Pad26)") (class "Default")
      (node (ref "U9") (pin "26") (pinfunction "PD6(T1/~{OC4D}/ADC9)_26") (pintype "bidirectional"))
    )
    (net (code "98") (name "unconnected-(U9-PD7(T0{slash}OC4D{slash}ADC10)-Pad27)") (class "Default")
      (node (ref "U9") (pin "27") (pinfunction "PD7(T0/OC4D/ADC10)_27") (pintype "bidirectional"))
    )
    (net (code "99") (name "unconnected-(U10D-O-Pad11)") (class "Default")
      (node (ref "U10") (pin "11") (pinfunction "O_11") (pintype "tri_state"))
    )
    (net (code "100") (name "unconnected-(USB-ID-Pad4)") (class "Default")
      (node (ref "USB") (pin "4") (pinfunction "ID_4") (pintype "bidirectional"))
    )
  )
)
